# fCPU_Controller1.net
KiCad netlist of a schematic drawn in EAGLE
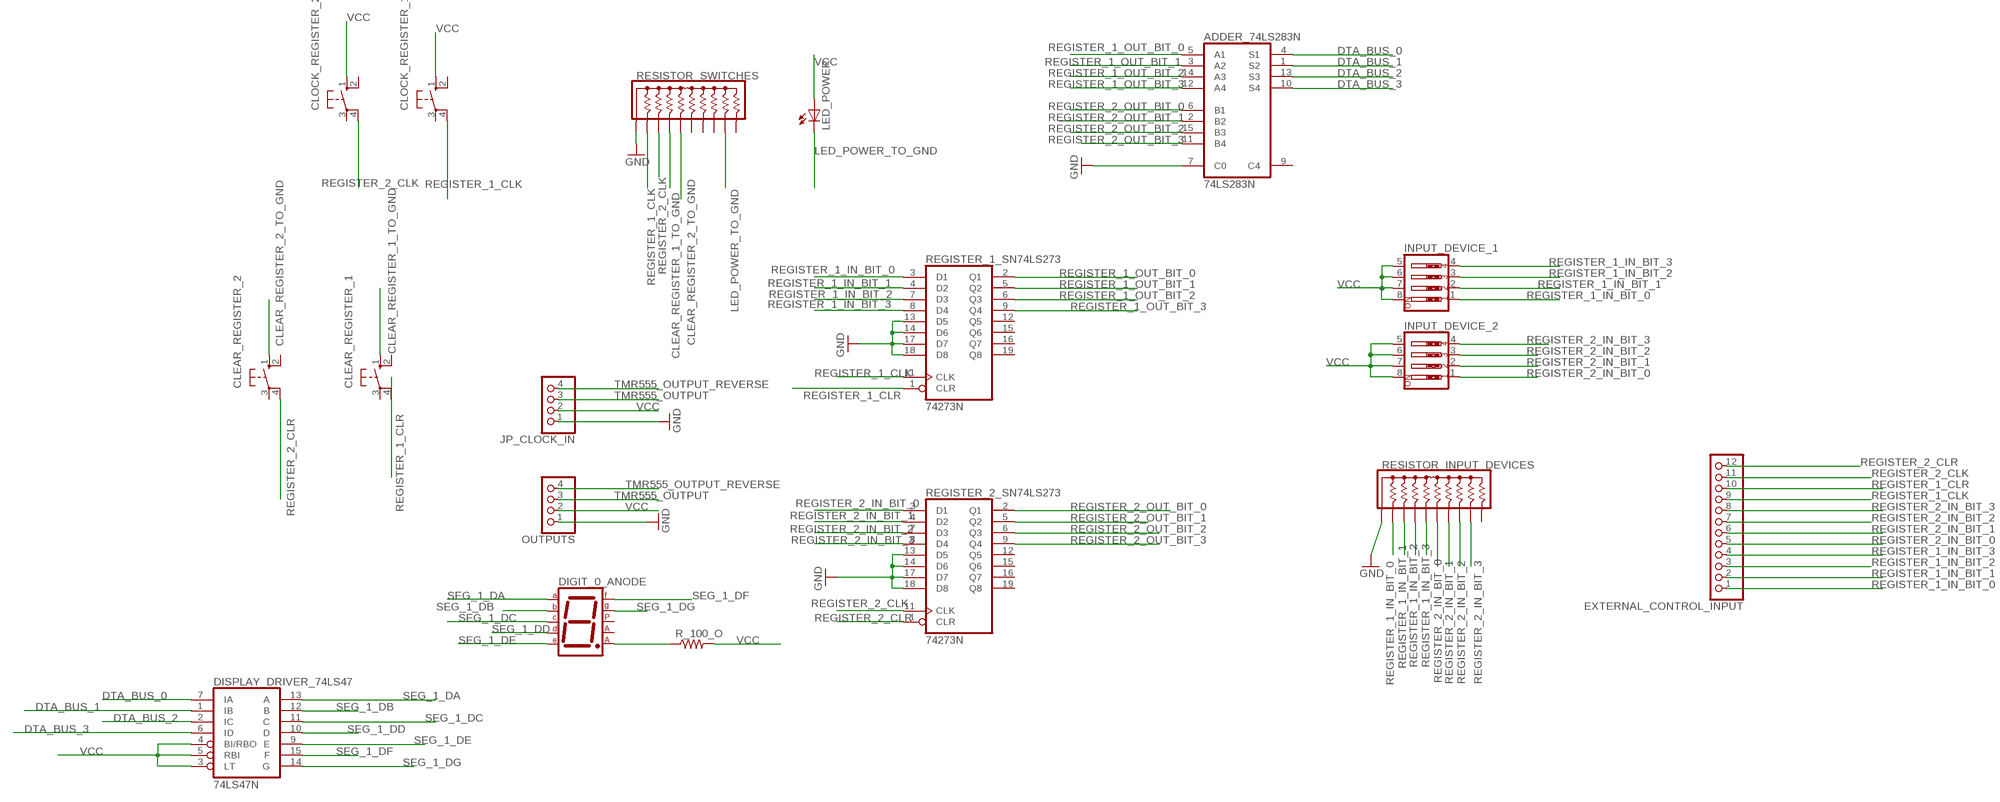
[diagram p0: schematic, sheet 1]

(export (version "E")
  (design (tool "Eeschema 10.0.6"))
  (components
    (comp (ref "ADDER_74LS283N")
      (value "74LS283N")
      (footprint "eagle-import:DIL16")
      (libsource (lib "eagle-import") (part "74283NLS"))
    )
    (comp (ref "CLEAR_REGISTER_1")
      (value "10-XX")
      (footprint "eagle-import:B3F-10XX")
      (fields (field (name "MPN") "B3F-1000"))
      (libsource (lib "eagle-import") (part "10-XX"))
    )
    (comp (ref "CLEAR_REGISTER_2")
      (value "10-XX")
      (footprint "eagle-import:B3F-10XX")
      (fields (field (name "MPN") "B3F-1000"))
      (libsource (lib "eagle-import") (part "10-XX"))
    )
    (comp (ref "CLOCK_REGISTER_1")
      (value "10-XX")
      (footprint "eagle-import:B3F-10XX")
      (fields (field (name "MPN") "B3F-1000"))
      (libsource (lib "eagle-import") (part "10-XX"))
    )
    (comp (ref "CLOCK_REGISTER_2")
      (value "10-XX")
      (footprint "eagle-import:B3F-10XX")
      (fields (field (name "MPN") "B3F-1000"))
      (libsource (lib "eagle-import") (part "10-XX"))
    )
    (comp (ref "DIGIT_0_ANODE")
      (value "7SEG-CA")
      (footprint "eagle-import:7SEG-13")
      (libsource (lib "eagle-import") (part "7SEG-CA"))
    )
    (comp (ref "DISPLAY_DRIVER_74LS47")
      (value "74LS47N")
      (footprint "eagle-import:DIL16")
      (libsource (lib "eagle-import") (part "7447NLS"))
    )
    (comp (ref "EXTERNAL_CONTROL_INPUT")
      (value "PINHD-1X12")
      (footprint "eagle-import:1X12")
      (libsource (lib "eagle-import") (part "PINHD-1X12"))
    )
    (comp (ref "INPUT_DEVICE_1")
      (value "SW_DIP-4")
      (footprint "eagle-import:EDG-04")
      (libsource (lib "eagle-import") (part "SW_DIP-4"))
    )
    (comp (ref "INPUT_DEVICE_2")
      (value "SW_DIP-4")
      (footprint "eagle-import:EDG-04")
      (libsource (lib "eagle-import") (part "SW_DIP-4"))
    )
    (comp (ref "JP_CLOCK_IN")
      (value "PINHD-1X4")
      (footprint "eagle-import:1X04")
      (libsource (lib "eagle-import") (part "PINHD-1X4"))
    )
    (comp (ref "LED_POWER")
      (value "LEDSMT1206")
      (footprint "eagle-import:1206")
      (libsource (lib "eagle-import") (part "LEDSMT1206"))
    )
    (comp (ref "OUTPUTS")
      (value "PINHD-1X4")
      (footprint "eagle-import:1X04")
      (libsource (lib "eagle-import") (part "PINHD-1X4"))
    )
    (comp (ref "REGISTER_1_SN74LS273")
      (value "74273N")
      (footprint "eagle-import:DIL20")
      (libsource (lib "eagle-import") (part "74273N"))
    )
    (comp (ref "REGISTER_2_SN74LS273")
      (value "74273N")
      (footprint "eagle-import:DIL20")
      (libsource (lib "eagle-import") (part "74273N"))
    )
    (comp (ref "RESISTOR_INPUT_DEVICES")
      (value "4610X")
      (footprint "eagle-import:SIP10")
      (libsource (lib "eagle-import") (part "4610X"))
    )
    (comp (ref "RESISTOR_SWITCHES")
      (value "4610X")
      (footprint "eagle-import:SIP10")
      (libsource (lib "eagle-import") (part "4610X"))
    )
    (comp (ref "R_100_O")
      (value "R-US_R1206")
      (footprint "eagle-import:R1206")
      (libsource (lib "eagle-import") (part "R-US_R1206"))
    )
  )
  (nets
    (net (code "1") (name "/CLEAR_REGISTER_1_TO_GND") (class "Default")
      (node (ref "CLEAR_REGISTER_1") (pin "1") (pinfunction "S_1") (pintype "passive"))
      (node (ref "RESISTOR_SWITCHES") (pin "4") (pinfunction "4_4") (pintype "passive"))
    )
    (net (code "2") (name "/CLEAR_REGISTER_2_TO_GND") (class "Default")
      (node (ref "CLEAR_REGISTER_2") (pin "1") (pinfunction "S_1") (pintype "passive"))
      (node (ref "RESISTOR_SWITCHES") (pin "5") (pinfunction "5_5") (pintype "passive"))
    )
    (net (code "3") (name "/DTA_BUS_0") (class "Default")
      (node (ref "ADDER_74LS283N") (pin "4") (pinfunction "S1_4") (pintype "output"))
      (node (ref "DISPLAY_DRIVER_74LS47") (pin "7") (pinfunction "IA_7") (pintype "input"))
    )
    (net (code "4") (name "/DTA_BUS_1") (class "Default")
      (node (ref "ADDER_74LS283N") (pin "1") (pinfunction "S2_1") (pintype "output"))
      (node (ref "DISPLAY_DRIVER_74LS47") (pin "1") (pinfunction "IB_1") (pintype "input"))
    )
    (net (code "5") (name "/DTA_BUS_2") (class "Default")
      (node (ref "ADDER_74LS283N") (pin "13") (pinfunction "S3_13") (pintype "output"))
      (node (ref "DISPLAY_DRIVER_74LS47") (pin "2") (pinfunction "IC_2") (pintype "input"))
    )
    (net (code "6") (name "/DTA_BUS_3") (class "Default")
      (node (ref "ADDER_74LS283N") (pin "10") (pinfunction "S4_10") (pintype "output"))
      (node (ref "DISPLAY_DRIVER_74LS47") (pin "6") (pinfunction "ID_6") (pintype "input"))
    )
    (net (code "7") (name "/LED_POWER_TO_GND") (class "Default")
      (node (ref "LED_POWER") (pin "C") (pinfunction "C_C") (pintype "passive"))
      (node (ref "RESISTOR_SWITCHES") (pin "9") (pinfunction "9_9") (pintype "passive"))
    )
    (net (code "8") (name "/REGISTER_1_CLK") (class "Default")
      (node (ref "CLOCK_REGISTER_1") (pin "4") (pinfunction "P1_4") (pintype "passive"))
      (node (ref "EXTERNAL_CONTROL_INPUT") (pin "9") (pinfunction "9_9") (pintype "passive"))
      (node (ref "REGISTER_1_SN74LS273") (pin "11") (pinfunction "CLK_11") (pintype "input"))
      (node (ref "RESISTOR_SWITCHES") (pin "2") (pinfunction "2_2") (pintype "passive"))
    )
    (net (code "9") (name "/REGISTER_1_CLR") (class "Default")
      (node (ref "CLEAR_REGISTER_1") (pin "4") (pinfunction "P1_4") (pintype "passive"))
      (node (ref "EXTERNAL_CONTROL_INPUT") (pin "10") (pinfunction "10_10") (pintype "passive"))
      (node (ref "REGISTER_1_SN74LS273") (pin "1") (pinfunction "CLR_1") (pintype "input"))
    )
    (net (code "10") (name "/REGISTER_1_IN_BIT_0") (class "Default")
      (node (ref "EXTERNAL_CONTROL_INPUT") (pin "1") (pinfunction "1_1") (pintype "passive"))
      (node (ref "INPUT_DEVICE_1") (pin "1") (pinfunction "1_1") (pintype "passive"))
      (node (ref "REGISTER_1_SN74LS273") (pin "3") (pinfunction "D1_3") (pintype "input"))
      (node (ref "RESISTOR_INPUT_DEVICES") (pin "2") (pinfunction "2_2") (pintype "passive"))
    )
    (net (code "11") (name "/REGISTER_1_IN_BIT_1") (class "Default")
      (node (ref "EXTERNAL_CONTROL_INPUT") (pin "2") (pinfunction "2_2") (pintype "passive"))
      (node (ref "INPUT_DEVICE_1") (pin "2") (pinfunction "2_2") (pintype "passive"))
      (node (ref "REGISTER_1_SN74LS273") (pin "4") (pinfunction "D2_4") (pintype "input"))
      (node (ref "RESISTOR_INPUT_DEVICES") (pin "3") (pinfunction "3_3") (pintype "passive"))
    )
    (net (code "12") (name "/REGISTER_1_IN_BIT_2") (class "Default")
      (node (ref "EXTERNAL_CONTROL_INPUT") (pin "3") (pinfunction "3_3") (pintype "passive"))
      (node (ref "INPUT_DEVICE_1") (pin "3") (pinfunction "3_3") (pintype "passive"))
      (node (ref "REGISTER_1_SN74LS273") (pin "7") (pinfunction "D3_7") (pintype "input"))
      (node (ref "RESISTOR_INPUT_DEVICES") (pin "4") (pinfunction "4_4") (pintype "passive"))
    )
    (net (code "13") (name "/REGISTER_1_IN_BIT_3") (class "Default")
      (node (ref "EXTERNAL_CONTROL_INPUT") (pin "4") (pinfunction "4_4") (pintype "passive"))
      (node (ref "INPUT_DEVICE_1") (pin "4") (pinfunction "4_4") (pintype "passive"))
      (node (ref "REGISTER_1_SN74LS273") (pin "8") (pinfunction "D4_8") (pintype "input"))
      (node (ref "RESISTOR_INPUT_DEVICES") (pin "5") (pinfunction "5_5") (pintype "passive"))
    )
    (net (code "14") (name "/REGISTER_1_OUT_BIT_0") (class "Default")
      (node (ref "ADDER_74LS283N") (pin "5") (pinfunction "A1_5") (pintype "input"))
      (node (ref "REGISTER_1_SN74LS273") (pin "2") (pinfunction "Q1_2") (pintype "output"))
    )
    (net (code "15") (name "/REGISTER_1_OUT_BIT_1") (class "Default")
      (node (ref "ADDER_74LS283N") (pin "3") (pinfunction "A2_3") (pintype "input"))
      (node (ref "REGISTER_1_SN74LS273") (pin "5") (pinfunction "Q2_5") (pintype "output"))
    )
    (net (code "16") (name "/REGISTER_1_OUT_BIT_2") (class "Default")
      (node (ref "ADDER_74LS283N") (pin "14") (pinfunction "A3_14") (pintype "input"))
      (node (ref "REGISTER_1_SN74LS273") (pin "6") (pinfunction "Q3_6") (pintype "output"))
    )
    (net (code "17") (name "/REGISTER_1_OUT_BIT_3") (class "Default")
      (node (ref "ADDER_74LS283N") (pin "12") (pinfunction "A4_12") (pintype "input"))
      (node (ref "REGISTER_1_SN74LS273") (pin "9") (pinfunction "Q4_9") (pintype "output"))
    )
    (net (code "18") (name "/REGISTER_2_CLK") (class "Default")
      (node (ref "CLOCK_REGISTER_2") (pin "4") (pinfunction "P1_4") (pintype "passive"))
      (node (ref "EXTERNAL_CONTROL_INPUT") (pin "11") (pinfunction "11_11") (pintype "passive"))
      (node (ref "REGISTER_2_SN74LS273") (pin "11") (pinfunction "CLK_11") (pintype "input"))
      (node (ref "RESISTOR_SWITCHES") (pin "3") (pinfunction "3_3") (pintype "passive"))
    )
    (net (code "19") (name "/REGISTER_2_CLR") (class "Default")
      (node (ref "CLEAR_REGISTER_2") (pin "4") (pinfunction "P1_4") (pintype "passive"))
      (node (ref "EXTERNAL_CONTROL_INPUT") (pin "12") (pinfunction "12_12") (pintype "passive"))
      (node (ref "REGISTER_2_SN74LS273") (pin "1") (pinfunction "CLR_1") (pintype "input"))
    )
    (net (code "20") (name "/REGISTER_2_IN_BIT_0") (class "Default")
      (node (ref "EXTERNAL_CONTROL_INPUT") (pin "5") (pinfunction "5_5") (pintype "passive"))
      (node (ref "INPUT_DEVICE_2") (pin "1") (pinfunction "1_1") (pintype "passive"))
      (node (ref "REGISTER_2_SN74LS273") (pin "3") (pinfunction "D1_3") (pintype "input"))
      (node (ref "RESISTOR_INPUT_DEVICES") (pin "6") (pinfunction "6_6") (pintype "passive"))
    )
    (net (code "21") (name "/REGISTER_2_IN_BIT_1") (class "Default")
      (node (ref "EXTERNAL_CONTROL_INPUT") (pin "6") (pinfunction "6_6") (pintype "passive"))
      (node (ref "INPUT_DEVICE_2") (pin "2") (pinfunction "2_2") (pintype "passive"))
      (node (ref "REGISTER_2_SN74LS273") (pin "4") (pinfunction "D2_4") (pintype "input"))
      (node (ref "RESISTOR_INPUT_DEVICES") (pin "7") (pinfunction "7_7") (pintype "passive"))
    )
    (net (code "22") (name "/REGISTER_2_IN_BIT_2") (class "Default")
      (node (ref "EXTERNAL_CONTROL_INPUT") (pin "7") (pinfunction "7_7") (pintype "passive"))
      (node (ref "INPUT_DEVICE_2") (pin "3") (pinfunction "3_3") (pintype "passive"))
      (node (ref "REGISTER_2_SN74LS273") (pin "7") (pinfunction "D3_7") (pintype "input"))
      (node (ref "RESISTOR_INPUT_DEVICES") (pin "8") (pinfunction "8_8") (pintype "passive"))
    )
    (net (code "23") (name "/REGISTER_2_IN_BIT_3") (class "Default")
      (node (ref "EXTERNAL_CONTROL_INPUT") (pin "8") (pinfunction "8_8") (pintype "passive"))
      (node (ref "INPUT_DEVICE_2") (pin "4") (pinfunction "4_4") (pintype "passive"))
      (node (ref "REGISTER_2_SN74LS273") (pin "8") (pinfunction "D4_8") (pintype "input"))
      (node (ref "RESISTOR_INPUT_DEVICES") (pin "9") (pinfunction "9_9") (pintype "passive"))
    )
    (net (code "24") (name "/REGISTER_2_OUT_BIT_0") (class "Default")
      (node (ref "ADDER_74LS283N") (pin "6") (pinfunction "B1_6") (pintype "input"))
      (node (ref "REGISTER_2_SN74LS273") (pin "2") (pinfunction "Q1_2") (pintype "output"))
    )
    (net (code "25") (name "/REGISTER_2_OUT_BIT_1") (class "Default")
      (node (ref "ADDER_74LS283N") (pin "2") (pinfunction "B2_2") (pintype "input"))
      (node (ref "REGISTER_2_SN74LS273") (pin "5") (pinfunction "Q2_5") (pintype "output"))
    )
    (net (code "26") (name "/REGISTER_2_OUT_BIT_2") (class "Default")
      (node (ref "ADDER_74LS283N") (pin "15") (pinfunction "B3_15") (pintype "input"))
      (node (ref "REGISTER_2_SN74LS273") (pin "6") (pinfunction "Q3_6") (pintype "output"))
    )
    (net (code "27") (name "/REGISTER_2_OUT_BIT_3") (class "Default")
      (node (ref "ADDER_74LS283N") (pin "11") (pinfunction "B4_11") (pintype "input"))
      (node (ref "REGISTER_2_SN74LS273") (pin "9") (pinfunction "Q4_9") (pintype "output"))
    )
    (net (code "28") (name "/SEG_1_DA") (class "Default")
      (node (ref "DIGIT_0_ANODE") (pin "7") (pinfunction "A_7") (pintype "passive"))
      (node (ref "DISPLAY_DRIVER_74LS47") (pin "13") (pinfunction "A_13") (pintype "output"))
    )
    (net (code "29") (name "/SEG_1_DB") (class "Default")
      (node (ref "DIGIT_0_ANODE") (pin "6") (pinfunction "B_6") (pintype "passive"))
      (node (ref "DISPLAY_DRIVER_74LS47") (pin "12") (pinfunction "B_12") (pintype "output"))
    )
    (net (code "30") (name "/SEG_1_DC") (class "Default")
      (node (ref "DIGIT_0_ANODE") (pin "4") (pinfunction "C_4") (pintype "passive"))
      (node (ref "DISPLAY_DRIVER_74LS47") (pin "11") (pinfunction "C_11") (pintype "output"))
    )
    (net (code "31") (name "/SEG_1_DD") (class "Default")
      (node (ref "DIGIT_0_ANODE") (pin "2") (pinfunction "D_2") (pintype "passive"))
      (node (ref "DISPLAY_DRIVER_74LS47") (pin "10") (pinfunction "D_10") (pintype "output"))
    )
    (net (code "32") (name "/SEG_1_DE") (class "Default")
      (node (ref "DIGIT_0_ANODE") (pin "1") (pinfunction "E_1") (pintype "passive"))
      (node (ref "DISPLAY_DRIVER_74LS47") (pin "9") (pinfunction "E_9") (pintype "output"))
    )
    (net (code "33") (name "/SEG_1_DF") (class "Default")
      (node (ref "DIGIT_0_ANODE") (pin "9") (pinfunction "F_9") (pintype "passive"))
      (node (ref "DISPLAY_DRIVER_74LS47") (pin "15") (pinfunction "F_15") (pintype "output"))
    )
    (net (code "34") (name "/SEG_1_DG") (class "Default")
      (node (ref "DIGIT_0_ANODE") (pin "10") (pinfunction "G_10") (pintype "passive"))
      (node (ref "DISPLAY_DRIVER_74LS47") (pin "14") (pinfunction "G_14") (pintype "output"))
    )
    (net (code "35") (name "/TMR555_OUTPUT") (class "Default")
      (node (ref "JP_CLOCK_IN") (pin "3") (pinfunction "3_3") (pintype "passive"))
      (node (ref "OUTPUTS") (pin "3") (pinfunction "3_3") (pintype "passive"))
    )
    (net (code "36") (name "/TMR555_OUTPUT_REVERSE") (class "Default")
      (node (ref "JP_CLOCK_IN") (pin "4") (pinfunction "4_4") (pintype "passive"))
      (node (ref "OUTPUTS") (pin "4") (pinfunction "4_4") (pintype "passive"))
    )
    (net (code "37") (name "/VCC") (class "Default")
      (node (ref "CLOCK_REGISTER_1") (pin "1") (pinfunction "S_1") (pintype "passive"))
      (node (ref "CLOCK_REGISTER_2") (pin "1") (pinfunction "S_1") (pintype "passive"))
      (node (ref "DISPLAY_DRIVER_74LS47") (pin "3") (pinfunction "LT_3") (pintype "input"))
      (node (ref "DISPLAY_DRIVER_74LS47") (pin "4") (pinfunction "BI/RBO_4") (pintype "input"))
      (node (ref "DISPLAY_DRIVER_74LS47") (pin "5") (pinfunction "RBI_5") (pintype "input"))
      (node (ref "INPUT_DEVICE_1") (pin "5") (pinfunction "5_5") (pintype "passive"))
      (node (ref "INPUT_DEVICE_1") (pin "6") (pinfunction "6_6") (pintype "passive"))
      (node (ref "INPUT_DEVICE_1") (pin "7") (pinfunction "7_7") (pintype "passive"))
      (node (ref "INPUT_DEVICE_1") (pin "8") (pinfunction "8_8") (pintype "passive"))
      (node (ref "INPUT_DEVICE_2") (pin "5") (pinfunction "5_5") (pintype "passive"))
      (node (ref "INPUT_DEVICE_2") (pin "6") (pinfunction "6_6") (pintype "passive"))
      (node (ref "INPUT_DEVICE_2") (pin "7") (pinfunction "7_7") (pintype "passive"))
      (node (ref "INPUT_DEVICE_2") (pin "8") (pinfunction "8_8") (pintype "passive"))
      (node (ref "JP_CLOCK_IN") (pin "2") (pinfunction "2_2") (pintype "passive"))
      (node (ref "LED_POWER") (pin "A") (pinfunction "A_A") (pintype "passive"))
      (node (ref "OUTPUTS") (pin "2") (pinfunction "2_2") (pintype "passive"))
      (node (ref "R_100_O") (pin "2") (pinfunction "2_2") (pintype "passive"))
    )
    (net (code "38") (name "GND") (class "Default")
      (node (ref "ADDER_74LS283N") (pin "7") (pinfunction "C0_7") (pintype "input"))
      (node (ref "JP_CLOCK_IN") (pin "1") (pinfunction "1_1") (pintype "passive"))
      (node (ref "OUTPUTS") (pin "1") (pinfunction "1_1") (pintype "passive"))
      (node (ref "REGISTER_1_SN74LS273") (pin "13") (pinfunction "D5_13") (pintype "input"))
      (node (ref "REGISTER_1_SN74LS273") (pin "14") (pinfunction "D6_14") (pintype "input"))
      (node (ref "REGISTER_1_SN74LS273") (pin "17") (pinfunction "D7_17") (pintype "input"))
      (node (ref "REGISTER_1_SN74LS273") (pin "18") (pinfunction "D8_18") (pintype "input"))
      (node (ref "REGISTER_2_SN74LS273") (pin "13") (pinfunction "D5_13") (pintype "input"))
      (node (ref "REGISTER_2_SN74LS273") (pin "14") (pinfunction "D6_14") (pintype "input"))
      (node (ref "REGISTER_2_SN74LS273") (pin "17") (pinfunction "D7_17") (pintype "input"))
      (node (ref "REGISTER_2_SN74LS273") (pin "18") (pinfunction "D8_18") (pintype "input"))
      (node (ref "RESISTOR_INPUT_DEVICES") (pin "1") (pinfunction "1_1") (pintype "passive"))
      (node (ref "RESISTOR_SWITCHES") (pin "1") (pinfunction "1_1") (pintype "passive"))
    )
    (net (code "39") (name "Net-(DIGIT_0_ANODE-CA2)") (class "Default")
      (node (ref "DIGIT_0_ANODE") (pin "8") (pinfunction "CA2_8") (pintype "passive"))
      (node (ref "R_100_O") (pin "1") (pinfunction "1_1") (pintype "passive"))
    )
    (net (code "40") (name "unconnected-(ADDER_74LS283NA-C4-Pad9)") (class "Default")
      (node (ref "ADDER_74LS283N") (pin "9") (pinfunction "C4_9") (pintype "output"))
    )
    (net (code "41") (name "unconnected-(CLEAR_REGISTER_1-P-Pad3)") (class "Default")
      (node (ref "CLEAR_REGISTER_1") (pin "3") (pinfunction "P_3") (pintype "passive"))
    )
    (net (code "42") (name "unconnected-(CLEAR_REGISTER_1-S1-Pad2)") (class "Default")
      (node (ref "CLEAR_REGISTER_1") (pin "2") (pinfunction "S1_2") (pintype "passive"))
    )
    (net (code "43") (name "unconnected-(CLEAR_REGISTER_2-P-Pad3)") (class "Default")
      (node (ref "CLEAR_REGISTER_2") (pin "3") (pinfunction "P_3") (pintype "passive"))
    )
    (net (code "44") (name "unconnected-(CLEAR_REGISTER_2-S1-Pad2)") (class "Default")
      (node (ref "CLEAR_REGISTER_2") (pin "2") (pinfunction "S1_2") (pintype "passive"))
    )
    (net (code "45") (name "unconnected-(CLOCK_REGISTER_1-P-Pad3)") (class "Default")
      (node (ref "CLOCK_REGISTER_1") (pin "3") (pinfunction "P_3") (pintype "passive"))
    )
    (net (code "46") (name "unconnected-(CLOCK_REGISTER_1-S1-Pad2)") (class "Default")
      (node (ref "CLOCK_REGISTER_1") (pin "2") (pinfunction "S1_2") (pintype "passive"))
    )
    (net (code "47") (name "unconnected-(CLOCK_REGISTER_2-P-Pad3)") (class "Default")
      (node (ref "CLOCK_REGISTER_2") (pin "3") (pinfunction "P_3") (pintype "passive"))
    )
    (net (code "48") (name "unconnected-(CLOCK_REGISTER_2-S1-Pad2)") (class "Default")
      (node (ref "CLOCK_REGISTER_2") (pin "2") (pinfunction "S1_2") (pintype "passive"))
    )
    (net (code "49") (name "unconnected-(DIGIT_0_ANODE-CA1-Pad3)") (class "Default")
      (node (ref "DIGIT_0_ANODE") (pin "3") (pinfunction "CA1_3") (pintype "passive"))
    )
    (net (code "50") (name "unconnected-(DIGIT_0_ANODE-DP-Pad5)") (class "Default")
      (node (ref "DIGIT_0_ANODE") (pin "5") (pinfunction "DP_5") (pintype "passive"))
    )
    (net (code "51") (name "unconnected-(REGISTER_1_SN74LS273A-Q5-Pad12)") (class "Default")
      (node (ref "REGISTER_1_SN74LS273") (pin "12") (pinfunction "Q5_12") (pintype "output"))
    )
    (net (code "52") (name "unconnected-(REGISTER_1_SN74LS273A-Q6-Pad15)") (class "Default")
      (node (ref "REGISTER_1_SN74LS273") (pin "15") (pinfunction "Q6_15") (pintype "output"))
    )
    (net (code "53") (name "unconnected-(REGISTER_1_SN74LS273A-Q7-Pad16)") (class "Default")
      (node (ref "REGISTER_1_SN74LS273") (pin "16") (pinfunction "Q7_16") (pintype "output"))
    )
    (net (code "54") (name "unconnected-(REGISTER_1_SN74LS273A-Q8-Pad19)") (class "Default")
      (node (ref "REGISTER_1_SN74LS273") (pin "19") (pinfunction "Q8_19") (pintype "output"))
    )
    (net (code "55") (name "unconnected-(REGISTER_2_SN74LS273A-Q5-Pad12)") (class "Default")
      (node (ref "REGISTER_2_SN74LS273") (pin "12") (pinfunction "Q5_12") (pintype "output"))
    )
    (net (code "56") (name "unconnected-(REGISTER_2_SN74LS273A-Q6-Pad15)") (class "Default")
      (node (ref "REGISTER_2_SN74LS273") (pin "15") (pinfunction "Q6_15") (pintype "output"))
    )
    (net (code "57") (name "unconnected-(REGISTER_2_SN74LS273A-Q7-Pad16)") (class "Default")
      (node (ref "REGISTER_2_SN74LS273") (pin "16") (pinfunction "Q7_16") (pintype "output"))
    )
    (net (code "58") (name "unconnected-(REGISTER_2_SN74LS273A-Q8-Pad19)") (class "Default")
      (node (ref "REGISTER_2_SN74LS273") (pin "19") (pinfunction "Q8_19") (pintype "output"))
    )
    (net (code "59") (name "unconnected-(RESISTOR_INPUT_DEVICES-Pad10)") (class "Default")
      (node (ref "RESISTOR_INPUT_DEVICES") (pin "10") (pinfunction "10_10") (pintype "passive"))
    )
    (net (code "60") (name "unconnected-(RESISTOR_SWITCHES-Pad6)") (class "Default")
      (node (ref "RESISTOR_SWITCHES") (pin "6") (pinfunction "6_6") (pintype "passive"))
    )
    (net (code "61") (name "unconnected-(RESISTOR_SWITCHES-Pad7)") (class "Default")
      (node (ref "RESISTOR_SWITCHES") (pin "7") (pinfunction "7_7") (pintype "passive"))
    )
    (net (code "62") (name "unconnected-(RESISTOR_SWITCHES-Pad8)") (class "Default")
      (node (ref "RESISTOR_SWITCHES") (pin "8") (pinfunction "8_8") (pintype "passive"))
    )
    (net (code "63") (name "unconnected-(RESISTOR_SWITCHES-Pad10)") (class "Default")
      (node (ref "RESISTOR_SWITCHES") (pin "10") (pinfunction "10_10") (pintype "passive"))
    )
  )
)
